# circuit.net
KiCad netlist of a schematic drawn in EAGLE
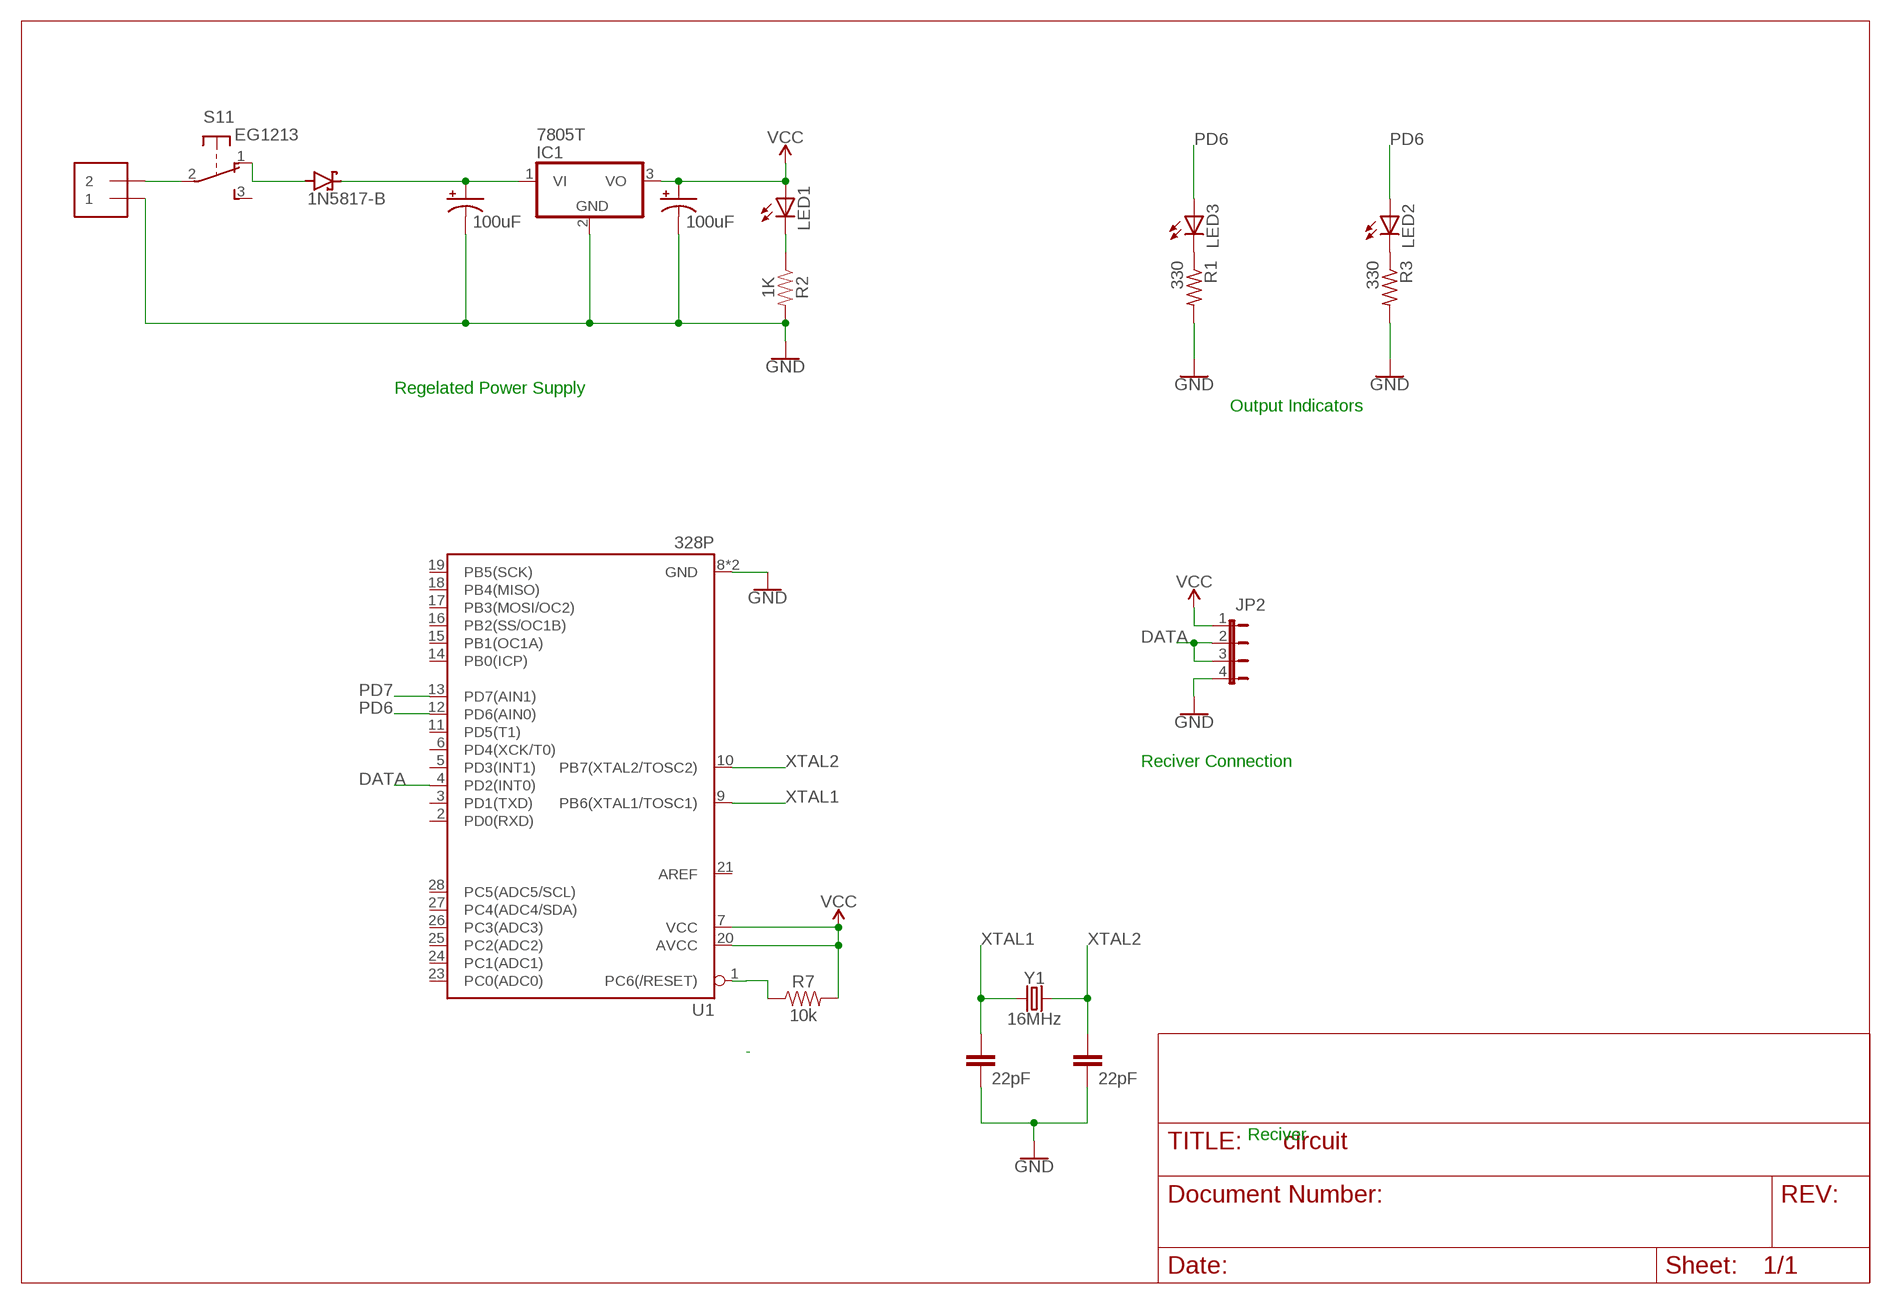
[diagram p0: schematic, sheet 1]

(export (version "E")
  (design (tool "Eeschema 10.0.6"))
  (components
    (comp (ref "$1_0_$_2023-02-20_05-34-40")
      (value "100uF")
      (footprint "eagle-import:CPOL-RADIAL-2.5MM-6.5MM")
      (libsource (lib "eagle-import") (part "100UF-POLAR-RADIAL-2.5MM-25V-20%"))
    )
    (comp (ref "$1_1_$_2023-02-20_05-34-40")
      (value "100uF")
      (footprint "eagle-import:CPOL-RADIAL-2.5MM-6.5MM")
      (libsource (lib "eagle-import") (part "100UF-POLAR-RADIAL-2.5MM-25V-20%"))
    )
    (comp (ref "$1_2_$_2023-02-20_05-34-40")
      (value "22pF")
      (footprint "eagle-import:CAP-PTH-2.54")
      (libsource (lib "eagle-import") (part "22PF-PTH-2.54MM-200V-5%"))
    )
    (comp (ref "$1_3_$_2023-02-20_05-34-40")
      (value "22pF")
      (footprint "eagle-import:CAP-PTH-2.54")
      (libsource (lib "eagle-import") (part "22PF-PTH-2.54MM-200V-5%"))
    )
    (comp (ref "$1_4_$_2023-02-20_05-34-40")
      (value "1N5817-B")
      (footprint "eagle-import:DO41-7.6")
      (libsource (lib "eagle-import") (part "1N5817-B"))
    )
    (comp (ref "IC1")
      (value "7805T")
      (footprint "eagle-import:TO220H")
      (libsource (lib "eagle-import") (part "78T05"))
    )
    (comp (ref "J1")
      (value "1X2-3.5MM")
      (footprint "eagle-import:1X2-3.5MM")
      (libsource (lib "eagle-import") (part "1X2-3.5MM"))
    )
    (comp (ref "JP2")
      (value "JP4E")
      (footprint "eagle-import:JP4")
      (libsource (lib "eagle-import") (part "JP4E"))
    )
    (comp (ref "LED1")
      (value "LED3MM")
      (footprint "eagle-import:LED3MM")
      (libsource (lib "eagle-import") (part "LED3MM"))
    )
    (comp (ref "LED2")
      (value "LED3MM")
      (footprint "eagle-import:LED3MM")
      (libsource (lib "eagle-import") (part "LED3MM"))
    )
    (comp (ref "LED3")
      (value "LED3MM")
      (footprint "eagle-import:LED3MM")
      (libsource (lib "eagle-import") (part "LED3MM"))
    )
    (comp (ref "R1")
      (value "330")
      (footprint "eagle-import:0207_5V")
      (libsource (lib "eagle-import") (part "R-US_0207/5V"))
    )
    (comp (ref "R2")
      (value "1K")
      (footprint "eagle-import:AXIAL-0.3")
      (libsource (lib "eagle-import") (part "RESISTORAXIAL-0.3"))
    )
    (comp (ref "R3")
      (value "330")
      (footprint "eagle-import:0207_5V")
      (libsource (lib "eagle-import") (part "R-US_0207/5V"))
    )
    (comp (ref "R7")
      (value "10k")
      (footprint "eagle-import:AXIAL-0.3")
      (libsource (lib "eagle-import") (part "RESISTORAXIAL-0.3"))
    )
    (comp (ref "S1")
      (value "EG1213")
      (footprint "eagle-import:EG1213")
      (libsource (lib "eagle-import") (part "EG1213"))
    )
    (comp (ref "U1")
      (value "328P")
      (footprint "eagle-import:DIP28")
      (libsource (lib "eagle-import") (part "ATMEGA328P_PDIP"))
    )
    (comp (ref "Y1")
      (value "16MHz")
      (footprint "eagle-import:HC49US")
      (libsource (lib "eagle-import") (part "CRYSTAL-16MHZPTH-HC49US"))
    )
  )
  (nets
    (net (code "1") (name "/DATA") (class "Default")
      (node (ref "JP2") (pin "2") (pinfunction "2_2") (pintype "passive"))
      (node (ref "JP2") (pin "3") (pinfunction "3_3") (pintype "passive"))
      (node (ref "U1") (pin "4") (pinfunction "PD2(INT0)_4") (pintype "bidirectional"))
    )
    (net (code "2") (name "/PD6") (class "Default")
      (node (ref "LED2") (pin "A") (pinfunction "A_A") (pintype "passive"))
      (node (ref "LED3") (pin "A") (pinfunction "A_A") (pintype "passive"))
      (node (ref "U1") (pin "12") (pinfunction "PD6(AIN0)_12") (pintype "bidirectional"))
    )
    (net (code "3") (name "/PD7") (class "Default")
      (node (ref "U1") (pin "13") (pinfunction "PD7(AIN1)_13") (pintype "bidirectional"))
    )
    (net (code "4") (name "/XTAL1") (class "Default")
      (node (ref "$1_2_$_2023-02-20_05-34-40") (pin "1") (pinfunction "1_1") (pintype "passive"))
      (node (ref "U1") (pin "9") (pinfunction "PB6(XTAL1/TOSC1)_9") (pintype "bidirectional"))
      (node (ref "Y1") (pin "1") (pinfunction "1_1") (pintype "passive"))
    )
    (net (code "5") (name "/XTAL2") (class "Default")
      (node (ref "$1_3_$_2023-02-20_05-34-40") (pin "1") (pinfunction "1_1") (pintype "passive"))
      (node (ref "U1") (pin "10") (pinfunction "PB7(XTAL2/TOSC2)_10") (pintype "bidirectional"))
      (node (ref "Y1") (pin "2") (pinfunction "2_2") (pintype "passive"))
    )
    (net (code "6") (name "GND") (class "Default")
      (node (ref "$1_0_$_2023-02-20_05-34-40") (pin "2") (pinfunction "-_2") (pintype "passive"))
      (node (ref "$1_1_$_2023-02-20_05-34-40") (pin "2") (pinfunction "-_2") (pintype "passive"))
      (node (ref "$1_2_$_2023-02-20_05-34-40") (pin "2") (pinfunction "2_2") (pintype "passive"))
      (node (ref "$1_3_$_2023-02-20_05-34-40") (pin "2") (pinfunction "2_2") (pintype "passive"))
      (node (ref "IC1") (pin "2") (pinfunction "GND_2") (pintype "passive"))
      (node (ref "J1") (pin "1") (pinfunction "1_1") (pintype "passive"))
      (node (ref "JP2") (pin "4") (pinfunction "4_4") (pintype "passive"))
      (node (ref "R1") (pin "2") (pinfunction "2_2") (pintype "passive"))
      (node (ref "R2") (pin "P$2") (pinfunction "2_P$2") (pintype "passive"))
      (node (ref "R3") (pin "2") (pinfunction "2_2") (pintype "passive"))
      (node (ref "U1") (pin "22") (pinfunction "GND_22") (pintype "bidirectional"))
      (node (ref "U1") (pin "8") (pinfunction "GND_8") (pintype "bidirectional"))
    )
    (net (code "7") (name "Net-($1_0_$_2023-02-20_05-34-40-+)") (class "Default")
      (node (ref "$1_0_$_2023-02-20_05-34-40") (pin "1") (pinfunction "+_1") (pintype "passive"))
      (node (ref "$1_4_$_2023-02-20_05-34-40") (pin "C") (pinfunction "C_C") (pintype "passive"))
      (node (ref "IC1") (pin "1") (pinfunction "VI_1") (pintype "input"))
    )
    (net (code "8") (name "Net-(LED1-C)") (class "Default")
      (node (ref "LED1") (pin "K") (pinfunction "C_K") (pintype "passive"))
      (node (ref "R2") (pin "P$1") (pinfunction "1_P$1") (pintype "passive"))
    )
    (net (code "9") (name "Net-(LED2-C)") (class "Default")
      (node (ref "LED2") (pin "K") (pinfunction "C_K") (pintype "passive"))
      (node (ref "R3") (pin "1") (pinfunction "1_1") (pintype "passive"))
    )
    (net (code "10") (name "Net-(LED3-C)") (class "Default")
      (node (ref "LED3") (pin "K") (pinfunction "C_K") (pintype "passive"))
      (node (ref "R1") (pin "1") (pinfunction "1_1") (pintype "passive"))
    )
    (net (code "11") (name "Net-(R7-1)") (class "Default")
      (node (ref "R7") (pin "P$1") (pinfunction "1_P$1") (pintype "passive"))
      (node (ref "U1") (pin "1") (pinfunction "PC6(/RESET)_1") (pintype "bidirectional"))
    )
    (net (code "12") (name "Net-(S1A-O)") (class "Default")
      (node (ref "$1_4_$_2023-02-20_05-34-40") (pin "A") (pinfunction "A_A") (pintype "passive"))
      (node (ref "S1") (pin "1") (pinfunction "O_1") (pintype "passive"))
    )
    (net (code "13") (name "Net-(S1A-P)") (class "Default")
      (node (ref "J1") (pin "2") (pinfunction "2_2") (pintype "passive"))
      (node (ref "S1") (pin "2") (pinfunction "P_2") (pintype "passive"))
    )
    (net (code "14") (name "VCC") (class "Default")
      (node (ref "$1_1_$_2023-02-20_05-34-40") (pin "1") (pinfunction "+_1") (pintype "passive"))
      (node (ref "IC1") (pin "3") (pinfunction "VO_3") (pintype "passive"))
      (node (ref "JP2") (pin "1") (pinfunction "1_1") (pintype "passive"))
      (node (ref "LED1") (pin "A") (pinfunction "A_A") (pintype "passive"))
      (node (ref "R7") (pin "P$2") (pinfunction "2_P$2") (pintype "passive"))
      (node (ref "U1") (pin "20") (pinfunction "AVCC_20") (pintype "bidirectional"))
      (node (ref "U1") (pin "7") (pinfunction "VCC_7") (pintype "bidirectional"))
    )
    (net (code "15") (name "unconnected-(S1A-S-Pad3)") (class "Default")
      (node (ref "S1") (pin "3") (pinfunction "S_3") (pintype "passive"))
    )
    (net (code "16") (name "unconnected-(U1-AREF-Pad21)") (class "Default")
      (node (ref "U1") (pin "21") (pinfunction "AREF_21") (pintype "bidirectional"))
    )
    (net (code "17") (name "unconnected-(U1-PB0(ICP)-Pad14)") (class "Default")
      (node (ref "U1") (pin "14") (pinfunction "PB0(ICP)_14") (pintype "bidirectional"))
    )
    (net (code "18") (name "unconnected-(U1-PB1(OC1A)-Pad15)") (class "Default")
      (node (ref "U1") (pin "15") (pinfunction "PB1(OC1A)_15") (pintype "bidirectional"))
    )
    (net (code "19") (name "unconnected-(U1-PB2(SS{slash}OC1B)-Pad16)") (class "Default")
      (node (ref "U1") (pin "16") (pinfunction "PB2(SS/OC1B)_16") (pintype "bidirectional"))
    )
    (net (code "20") (name "unconnected-(U1-PB3(MOSI{slash}OC2)-Pad17)") (class "Default")
      (node (ref "U1") (pin "17") (pinfunction "PB3(MOSI/OC2)_17") (pintype "bidirectional"))
    )
    (net (code "21") (name "unconnected-(U1-PB4(MISO)-Pad18)") (class "Default")
      (node (ref "U1") (pin "18") (pinfunction "PB4(MISO)_18") (pintype "bidirectional"))
    )
    (net (code "22") (name "unconnected-(U1-PB5(SCK)-Pad19)") (class "Default")
      (node (ref "U1") (pin "19") (pinfunction "PB5(SCK)_19") (pintype "bidirectional"))
    )
    (net (code "23") (name "unconnected-(U1-PC0(ADC0)-Pad23)") (class "Default")
      (node (ref "U1") (pin "23") (pinfunction "PC0(ADC0)_23") (pintype "bidirectional"))
    )
    (net (code "24") (name "unconnected-(U1-PC1(ADC1)-Pad24)") (class "Default")
      (node (ref "U1") (pin "24") (pinfunction "PC1(ADC1)_24") (pintype "bidirectional"))
    )
    (net (code "25") (name "unconnected-(U1-PC2(ADC2)-Pad25)") (class "Default")
      (node (ref "U1") (pin "25") (pinfunction "PC2(ADC2)_25") (pintype "bidirectional"))
    )
    (net (code "26") (name "unconnected-(U1-PC3(ADC3)-Pad26)") (class "Default")
      (node (ref "U1") (pin "26") (pinfunction "PC3(ADC3)_26") (pintype "bidirectional"))
    )
    (net (code "27") (name "unconnected-(U1-PC4(ADC4{slash}SDA)-Pad27)") (class "Default")
      (node (ref "U1") (pin "27") (pinfunction "PC4(ADC4/SDA)_27") (pintype "bidirectional"))
    )
    (net (code "28") (name "unconnected-(U1-PC5(ADC5{slash}SCL)-Pad28)") (class "Default")
      (node (ref "U1") (pin "28") (pinfunction "PC5(ADC5/SCL)_28") (pintype "bidirectional"))
    )
    (net (code "29") (name "unconnected-(U1-PD0(RXD)-Pad2)") (class "Default")
      (node (ref "U1") (pin "2") (pinfunction "PD0(RXD)_2") (pintype "bidirectional"))
    )
    (net (code "30") (name "unconnected-(U1-PD1(TXD)-Pad3)") (class "Default")
      (node (ref "U1") (pin "3") (pinfunction "PD1(TXD)_3") (pintype "bidirectional"))
    )
    (net (code "31") (name "unconnected-(U1-PD3(INT1)-Pad5)") (class "Default")
      (node (ref "U1") (pin "5") (pinfunction "PD3(INT1)_5") (pintype "bidirectional"))
    )
    (net (code "32") (name "unconnected-(U1-PD4(XCK{slash}T0)-Pad6)") (class "Default")
      (node (ref "U1") (pin "6") (pinfunction "PD4(XCK/T0)_6") (pintype "bidirectional"))
    )
    (net (code "33") (name "unconnected-(U1-PD5(T1)-Pad11)") (class "Default")
      (node (ref "U1") (pin "11") (pinfunction "PD5(T1)_11") (pintype "bidirectional"))
    )
  )
)
